# AgitPOV_WiFi.net
KiCad netlist of a schematic drawn in EAGLE
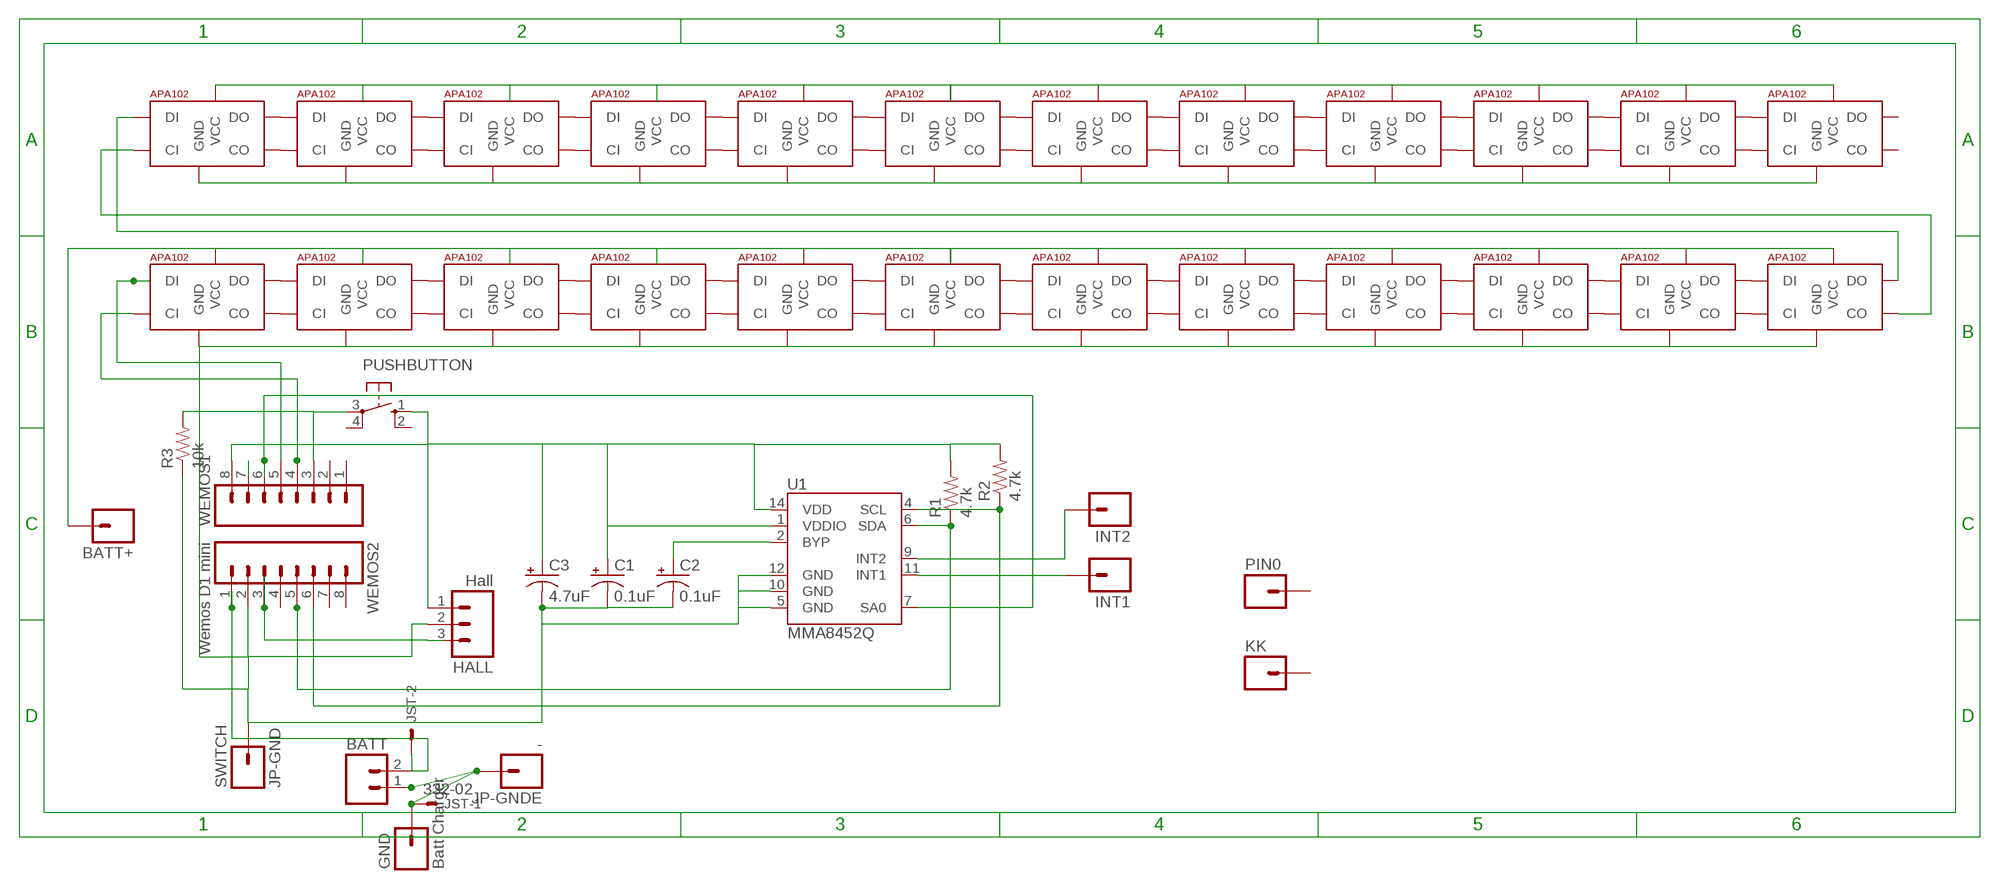
[diagram p0: schematic, sheet 1]

(export (version "E")
  (design (tool "Eeschema 10.0.6"))
  (components
    (comp (ref "BATT")
      (value "M02LOCK_LONGPADS")
      (footprint "eagle-import:1X02_LOCK_LONGPADS")
      (libsource (lib "eagle-import") (part "M02LOCK_LONGPADS"))
    )
    (comp (ref "BATT+")
      (value "M01PTH")
      (footprint "eagle-import:1X01")
      (libsource (lib "eagle-import") (part "M01PTH"))
    )
    (comp (ref "C1")
      (value "0.1uF")
      (footprint "eagle-import:EIA3216")
      (libsource (lib "eagle-import") (part "10UF-16V-10%(TANT)"))
    )
    (comp (ref "C2")
      (value "0.1uF")
      (footprint "eagle-import:EIA3216")
      (libsource (lib "eagle-import") (part "10UF-16V-10%(TANT)"))
    )
    (comp (ref "C3")
      (value "4.7uF")
      (footprint "eagle-import:EIA3216")
      (libsource (lib "eagle-import") (part "10UF-16V-10%(TANT)"))
    )
    (comp (ref "DEL1")
      (value "APA1025050")
      (footprint "eagle-import:APA102_5050")
      (libsource (lib "eagle-import") (part "APA1025050"))
    )
    (comp (ref "DEL2")
      (value "APA1025050")
      (footprint "eagle-import:APA102_5050")
      (libsource (lib "eagle-import") (part "APA1025050"))
    )
    (comp (ref "DEL3")
      (value "APA1025050")
      (footprint "eagle-import:APA102_5050")
      (libsource (lib "eagle-import") (part "APA1025050"))
    )
    (comp (ref "DEL4")
      (value "APA1025050")
      (footprint "eagle-import:APA102_5050")
      (libsource (lib "eagle-import") (part "APA1025050"))
    )
    (comp (ref "DEL5")
      (value "APA1025050")
      (footprint "eagle-import:APA102_5050")
      (libsource (lib "eagle-import") (part "APA1025050"))
    )
    (comp (ref "DEL6")
      (value "APA1025050")
      (footprint "eagle-import:APA102_5050")
      (libsource (lib "eagle-import") (part "APA1025050"))
    )
    (comp (ref "DEL7")
      (value "APA1025050")
      (footprint "eagle-import:APA102_5050")
      (libsource (lib "eagle-import") (part "APA1025050"))
    )
    (comp (ref "DEL8")
      (value "APA1025050")
      (footprint "eagle-import:APA102_5050")
      (libsource (lib "eagle-import") (part "APA1025050"))
    )
    (comp (ref "DEL9")
      (value "APA1025050")
      (footprint "eagle-import:APA102_5050")
      (libsource (lib "eagle-import") (part "APA1025050"))
    )
    (comp (ref "DEL10")
      (value "APA1025050")
      (footprint "eagle-import:APA102_5050")
      (libsource (lib "eagle-import") (part "APA1025050"))
    )
    (comp (ref "DEL11")
      (value "APA1025050")
      (footprint "eagle-import:APA102_5050")
      (libsource (lib "eagle-import") (part "APA1025050"))
    )
    (comp (ref "DEL12")
      (value "APA1025050")
      (footprint "eagle-import:APA102_5050")
      (libsource (lib "eagle-import") (part "APA1025050"))
    )
    (comp (ref "DEL13")
      (value "APA1025050")
      (footprint "eagle-import:APA102_5050")
      (libsource (lib "eagle-import") (part "APA1025050"))
    )
    (comp (ref "DEL15")
      (value "APA1025050")
      (footprint "eagle-import:APA102_5050")
      (libsource (lib "eagle-import") (part "APA1025050"))
    )
    (comp (ref "DEL16")
      (value "APA1025050")
      (footprint "eagle-import:APA102_5050")
      (libsource (lib "eagle-import") (part "APA1025050"))
    )
    (comp (ref "DEL17")
      (value "APA1025050")
      (footprint "eagle-import:APA102_5050")
      (libsource (lib "eagle-import") (part "APA1025050"))
    )
    (comp (ref "DEL18")
      (value "APA1025050")
      (footprint "eagle-import:APA102_5050")
      (libsource (lib "eagle-import") (part "APA1025050"))
    )
    (comp (ref "DEL19")
      (value "APA1025050")
      (footprint "eagle-import:APA102_5050")
      (libsource (lib "eagle-import") (part "APA1025050"))
    )
    (comp (ref "DEL20")
      (value "APA1025050")
      (footprint "eagle-import:APA102_5050")
      (libsource (lib "eagle-import") (part "APA1025050"))
    )
    (comp (ref "DEL21")
      (value "APA1025050")
      (footprint "eagle-import:APA102_5050")
      (libsource (lib "eagle-import") (part "APA1025050"))
    )
    (comp (ref "DEL22")
      (value "APA1025050")
      (footprint "eagle-import:APA102_5050")
      (libsource (lib "eagle-import") (part "APA1025050"))
    )
    (comp (ref "DEL23")
      (value "APA1025050")
      (footprint "eagle-import:APA102_5050")
      (libsource (lib "eagle-import") (part "APA1025050"))
    )
    (comp (ref "DEL24")
      (value "APA1025050")
      (footprint "eagle-import:APA102_5050")
      (libsource (lib "eagle-import") (part "APA1025050"))
    )
    (comp (ref "FFFFF")
      (value "APA1025050")
      (footprint "eagle-import:APA102_5050")
      (libsource (lib "eagle-import") (part "APA1025050"))
    )
    (comp (ref "GND")
      (value "Batt Charger")
      (footprint "eagle-import:1X01")
      (libsource (lib "eagle-import") (part "M01PTH"))
    )
    (comp (ref "HALL")
      (value "Hall")
      (footprint "eagle-import:1X03")
      (libsource (lib "eagle-import") (part "M03PTH"))
    )
    (comp (ref "INT1")
      (value "M01PTH")
      (footprint "eagle-import:1X01")
      (libsource (lib "eagle-import") (part "M01PTH"))
    )
    (comp (ref "INT2")
      (value "M01PTH")
      (footprint "eagle-import:1X01")
      (libsource (lib "eagle-import") (part "M01PTH"))
    )
    (comp (ref "JP-GND")
      (value "SWITCH")
      (footprint "eagle-import:1X01")
      (libsource (lib "eagle-import") (part "M01PTH"))
    )
    (comp (ref "JP-GNDE")
      (value "-")
      (footprint "eagle-import:1X01")
      (libsource (lib "eagle-import") (part "M01PTH"))
    )
    (comp (ref "JST")
      (value "332-02")
      (footprint "eagle-import:332-02")
      (libsource (lib "eagle-import") (part "332-02"))
    )
    (comp (ref "KK")
      (value "M01PTH")
      (footprint "eagle-import:1X01")
      (libsource (lib "eagle-import") (part "M01PTH"))
    )
    (comp (ref "PIN0")
      (value "M01PTH")
      (footprint "eagle-import:1X01")
      (libsource (lib "eagle-import") (part "M01PTH"))
    )
    (comp (ref "PUSHBUTTON")
      (value "10-XX")
      (footprint "eagle-import:B3F-10XX")
      (fields (field (name "MPN") "B3F-1000"))
      (libsource (lib "eagle-import") (part "10-XX"))
    )
    (comp (ref "R1")
      (value "4.7k")
      (footprint "eagle-import:1206")
      (libsource (lib "eagle-import") (part "RESISTOR1206"))
    )
    (comp (ref "R2")
      (value "4.7k")
      (footprint "eagle-import:1206")
      (libsource (lib "eagle-import") (part "RESISTOR1206"))
    )
    (comp (ref "R3")
      (value "10k")
      (footprint "eagle-import:1206")
      (libsource (lib "eagle-import") (part "RESISTOR1206"))
    )
    (comp (ref "U1")
      (value "MMA8452Q")
      (footprint "eagle-import:QFN-16_0.5MM")
      (libsource (lib "eagle-import") (part "MMA8452Q"))
    )
    (comp (ref "WEMOS1")
      (value "M08")
      (footprint "eagle-import:1X08_ROUND")
      (libsource (lib "eagle-import") (part "M08"))
    )
    (comp (ref "WEMOS2")
      (value "Wemos D1 mini")
      (footprint "eagle-import:1X08_ROUND")
      (libsource (lib "eagle-import") (part "M08"))
    )
  )
  (nets
    (net (code "1") (name "/5V") (class "Default")
      (node (ref "BATT") (pin "2") (pinfunction "2_2") (pintype "passive"))
      (node (ref "BATT+") (pin "1") (pinfunction "1_1") (pintype "passive"))
      (node (ref "DEL1") (pin "1") (pinfunction "VCC_1") (pintype "bidirectional"))
      (node (ref "DEL10") (pin "1") (pinfunction "VCC_1") (pintype "bidirectional"))
      (node (ref "DEL11") (pin "1") (pinfunction "VCC_1") (pintype "bidirectional"))
      (node (ref "DEL12") (pin "1") (pinfunction "VCC_1") (pintype "bidirectional"))
      (node (ref "DEL13") (pin "1") (pinfunction "VCC_1") (pintype "bidirectional"))
      (node (ref "DEL15") (pin "1") (pinfunction "VCC_1") (pintype "bidirectional"))
      (node (ref "DEL16") (pin "1") (pinfunction "VCC_1") (pintype "bidirectional"))
      (node (ref "DEL17") (pin "1") (pinfunction "VCC_1") (pintype "bidirectional"))
      (node (ref "DEL18") (pin "1") (pinfunction "VCC_1") (pintype "bidirectional"))
      (node (ref "DEL19") (pin "1") (pinfunction "VCC_1") (pintype "bidirectional"))
      (node (ref "DEL2") (pin "1") (pinfunction "VCC_1") (pintype "bidirectional"))
      (node (ref "DEL20") (pin "1") (pinfunction "VCC_1") (pintype "bidirectional"))
      (node (ref "DEL21") (pin "1") (pinfunction "VCC_1") (pintype "bidirectional"))
      (node (ref "DEL22") (pin "1") (pinfunction "VCC_1") (pintype "bidirectional"))
      (node (ref "DEL23") (pin "1") (pinfunction "VCC_1") (pintype "bidirectional"))
      (node (ref "DEL24") (pin "1") (pinfunction "VCC_1") (pintype "bidirectional"))
      (node (ref "DEL3") (pin "1") (pinfunction "VCC_1") (pintype "bidirectional"))
      (node (ref "DEL4") (pin "1") (pinfunction "VCC_1") (pintype "bidirectional"))
      (node (ref "DEL5") (pin "1") (pinfunction "VCC_1") (pintype "bidirectional"))
      (node (ref "DEL6") (pin "1") (pinfunction "VCC_1") (pintype "bidirectional"))
      (node (ref "DEL7") (pin "1") (pinfunction "VCC_1") (pintype "bidirectional"))
      (node (ref "DEL8") (pin "1") (pinfunction "VCC_1") (pintype "bidirectional"))
      (node (ref "DEL9") (pin "1") (pinfunction "VCC_1") (pintype "bidirectional"))
      (node (ref "FFFFF") (pin "1") (pinfunction "VCC_1") (pintype "bidirectional"))
      (node (ref "JST") (pin "2") (pinfunction "S_2") (pintype "passive"))
      (node (ref "WEMOS2") (pin "1") (pinfunction "1_1") (pintype "passive"))
    )
    (net (code "2") (name "/GND") (class "Default")
      (node (ref "C1") (pin "C") (pinfunction "-_C") (pintype "passive"))
      (node (ref "C2") (pin "C") (pinfunction "-_C") (pintype "passive"))
      (node (ref "C3") (pin "C") (pinfunction "-_C") (pintype "passive"))
      (node (ref "DEL1") (pin "6") (pinfunction "GND_6") (pintype "bidirectional"))
      (node (ref "DEL10") (pin "6") (pinfunction "GND_6") (pintype "bidirectional"))
      (node (ref "DEL11") (pin "6") (pinfunction "GND_6") (pintype "bidirectional"))
      (node (ref "DEL12") (pin "6") (pinfunction "GND_6") (pintype "bidirectional"))
      (node (ref "DEL13") (pin "6") (pinfunction "GND_6") (pintype "bidirectional"))
      (node (ref "DEL15") (pin "6") (pinfunction "GND_6") (pintype "bidirectional"))
      (node (ref "DEL16") (pin "6") (pinfunction "GND_6") (pintype "bidirectional"))
      (node (ref "DEL17") (pin "6") (pinfunction "GND_6") (pintype "bidirectional"))
      (node (ref "DEL18") (pin "6") (pinfunction "GND_6") (pintype "bidirectional"))
      (node (ref "DEL19") (pin "6") (pinfunction "GND_6") (pintype "bidirectional"))
      (node (ref "DEL2") (pin "6") (pinfunction "GND_6") (pintype "bidirectional"))
      (node (ref "DEL20") (pin "6") (pinfunction "GND_6") (pintype "bidirectional"))
      (node (ref "DEL21") (pin "6") (pinfunction "GND_6") (pintype "bidirectional"))
      (node (ref "DEL22") (pin "6") (pinfunction "GND_6") (pintype "bidirectional"))
      (node (ref "DEL23") (pin "6") (pinfunction "GND_6") (pintype "bidirectional"))
      (node (ref "DEL24") (pin "6") (pinfunction "GND_6") (pintype "bidirectional"))
      (node (ref "DEL3") (pin "6") (pinfunction "GND_6") (pintype "bidirectional"))
      (node (ref "DEL4") (pin "6") (pinfunction "GND_6") (pintype "bidirectional"))
      (node (ref "DEL5") (pin "6") (pinfunction "GND_6") (pintype "bidirectional"))
      (node (ref "DEL6") (pin "6") (pinfunction "GND_6") (pintype "bidirectional"))
      (node (ref "DEL7") (pin "6") (pinfunction "GND_6") (pintype "bidirectional"))
      (node (ref "DEL8") (pin "6") (pinfunction "GND_6") (pintype "bidirectional"))
      (node (ref "DEL9") (pin "6") (pinfunction "GND_6") (pintype "bidirectional"))
      (node (ref "FFFFF") (pin "6") (pinfunction "GND_6") (pintype "bidirectional"))
      (node (ref "HALL") (pin "2") (pinfunction "2_2") (pintype "passive"))
      (node (ref "JP-GND") (pin "1") (pinfunction "1_1") (pintype "passive"))
      (node (ref "R3") (pin "1") (pinfunction "1_1") (pintype "passive"))
      (node (ref "U1") (pin "10") (pinfunction "GND_10") (pintype "bidirectional"))
      (node (ref "U1") (pin "12") (pinfunction "GND_12") (pintype "bidirectional"))
      (node (ref "U1") (pin "5") (pinfunction "GND_5") (pintype "bidirectional"))
      (node (ref "WEMOS2") (pin "2") (pinfunction "2_2") (pintype "passive"))
    )
    (net (code "3") (name "Net-(C1-+)") (class "Default")
      (node (ref "C1") (pin "A") (pinfunction "+_A") (pintype "passive"))
      (node (ref "C3") (pin "A") (pinfunction "+_A") (pintype "passive"))
      (node (ref "HALL") (pin "1") (pinfunction "1_1") (pintype "passive"))
      (node (ref "PUSHBUTTON") (pin "1") (pinfunction "S_1") (pintype "passive"))
      (node (ref "R1") (pin "2") (pinfunction "2_2") (pintype "passive"))
      (node (ref "R2") (pin "2") (pinfunction "2_2") (pintype "passive"))
      (node (ref "U1") (pin "1") (pinfunction "VDDIO_1") (pintype "bidirectional"))
      (node (ref "U1") (pin "14") (pinfunction "VDD_14") (pintype "bidirectional"))
      (node (ref "WEMOS1") (pin "8") (pinfunction "8_8") (pintype "passive"))
    )
    (net (code "4") (name "Net-(C2-+)") (class "Default")
      (node (ref "C2") (pin "A") (pinfunction "+_A") (pintype "passive"))
      (node (ref "U1") (pin "2") (pinfunction "BYP_2") (pintype "bidirectional"))
    )
    (net (code "5") (name "Net-(DEL1-CI)") (class "Default")
      (node (ref "DEL1") (pin "5") (pinfunction "CI_5") (pintype "bidirectional"))
      (node (ref "WEMOS1") (pin "4") (pinfunction "4_4") (pintype "passive"))
    )
    (net (code "6") (name "Net-(DEL1-CO)") (class "Default")
      (node (ref "DEL1") (pin "2") (pinfunction "CO_2") (pintype "bidirectional"))
      (node (ref "DEL2") (pin "5") (pinfunction "CI_5") (pintype "bidirectional"))
    )
    (net (code "7") (name "Net-(DEL1-DI)") (class "Default")
      (node (ref "DEL1") (pin "4") (pinfunction "DI_4") (pintype "bidirectional"))
      (node (ref "WEMOS1") (pin "5") (pinfunction "5_5") (pintype "passive"))
    )
    (net (code "8") (name "Net-(DEL1-DO)") (class "Default")
      (node (ref "DEL1") (pin "3") (pinfunction "DO_3") (pintype "bidirectional"))
      (node (ref "DEL2") (pin "4") (pinfunction "DI_4") (pintype "bidirectional"))
    )
    (net (code "9") (name "Net-(DEL2-CO)") (class "Default")
      (node (ref "DEL2") (pin "2") (pinfunction "CO_2") (pintype "bidirectional"))
      (node (ref "DEL3") (pin "5") (pinfunction "CI_5") (pintype "bidirectional"))
    )
    (net (code "10") (name "Net-(DEL2-DO)") (class "Default")
      (node (ref "DEL2") (pin "3") (pinfunction "DO_3") (pintype "bidirectional"))
      (node (ref "DEL3") (pin "4") (pinfunction "DI_4") (pintype "bidirectional"))
    )
    (net (code "11") (name "Net-(DEL3-CO)") (class "Default")
      (node (ref "DEL3") (pin "2") (pinfunction "CO_2") (pintype "bidirectional"))
      (node (ref "DEL4") (pin "5") (pinfunction "CI_5") (pintype "bidirectional"))
    )
    (net (code "12") (name "Net-(DEL3-DO)") (class "Default")
      (node (ref "DEL3") (pin "3") (pinfunction "DO_3") (pintype "bidirectional"))
      (node (ref "DEL4") (pin "4") (pinfunction "DI_4") (pintype "bidirectional"))
    )
    (net (code "13") (name "Net-(DEL4-CO)") (class "Default")
      (node (ref "DEL4") (pin "2") (pinfunction "CO_2") (pintype "bidirectional"))
      (node (ref "DEL5") (pin "5") (pinfunction "CI_5") (pintype "bidirectional"))
    )
    (net (code "14") (name "Net-(DEL4-DO)") (class "Default")
      (node (ref "DEL4") (pin "3") (pinfunction "DO_3") (pintype "bidirectional"))
      (node (ref "DEL5") (pin "4") (pinfunction "DI_4") (pintype "bidirectional"))
    )
    (net (code "15") (name "Net-(DEL5-CO)") (class "Default")
      (node (ref "DEL5") (pin "2") (pinfunction "CO_2") (pintype "bidirectional"))
      (node (ref "DEL6") (pin "5") (pinfunction "CI_5") (pintype "bidirectional"))
    )
    (net (code "16") (name "Net-(DEL5-DO)") (class "Default")
      (node (ref "DEL5") (pin "3") (pinfunction "DO_3") (pintype "bidirectional"))
      (node (ref "DEL6") (pin "4") (pinfunction "DI_4") (pintype "bidirectional"))
    )
    (net (code "17") (name "Net-(DEL6-CO)") (class "Default")
      (node (ref "DEL6") (pin "2") (pinfunction "CO_2") (pintype "bidirectional"))
      (node (ref "DEL7") (pin "5") (pinfunction "CI_5") (pintype "bidirectional"))
    )
    (net (code "18") (name "Net-(DEL6-DO)") (class "Default")
      (node (ref "DEL6") (pin "3") (pinfunction "DO_3") (pintype "bidirectional"))
      (node (ref "DEL7") (pin "4") (pinfunction "DI_4") (pintype "bidirectional"))
    )
    (net (code "19") (name "Net-(DEL7-CO)") (class "Default")
      (node (ref "DEL7") (pin "2") (pinfunction "CO_2") (pintype "bidirectional"))
      (node (ref "DEL8") (pin "5") (pinfunction "CI_5") (pintype "bidirectional"))
    )
    (net (code "20") (name "Net-(DEL7-DO)") (class "Default")
      (node (ref "DEL7") (pin "3") (pinfunction "DO_3") (pintype "bidirectional"))
      (node (ref "DEL8") (pin "4") (pinfunction "DI_4") (pintype "bidirectional"))
    )
    (net (code "21") (name "Net-(DEL8-CO)") (class "Default")
      (node (ref "DEL8") (pin "2") (pinfunction "CO_2") (pintype "bidirectional"))
      (node (ref "DEL9") (pin "5") (pinfunction "CI_5") (pintype "bidirectional"))
    )
    (net (code "22") (name "Net-(DEL8-DO)") (class "Default")
      (node (ref "DEL8") (pin "3") (pinfunction "DO_3") (pintype "bidirectional"))
      (node (ref "DEL9") (pin "4") (pinfunction "DI_4") (pintype "bidirectional"))
    )
    (net (code "23") (name "Net-(DEL10-CI)") (class "Default")
      (node (ref "DEL10") (pin "5") (pinfunction "CI_5") (pintype "bidirectional"))
      (node (ref "DEL9") (pin "2") (pinfunction "CO_2") (pintype "bidirectional"))
    )
    (net (code "24") (name "Net-(DEL10-CO)") (class "Default")
      (node (ref "DEL10") (pin "2") (pinfunction "CO_2") (pintype "bidirectional"))
      (node (ref "DEL11") (pin "5") (pinfunction "CI_5") (pintype "bidirectional"))
    )
    (net (code "25") (name "Net-(DEL10-DI)") (class "Default")
      (node (ref "DEL10") (pin "4") (pinfunction "DI_4") (pintype "bidirectional"))
      (node (ref "DEL9") (pin "3") (pinfunction "DO_3") (pintype "bidirectional"))
    )
    (net (code "26") (name "Net-(DEL10-DO)") (class "Default")
      (node (ref "DEL10") (pin "3") (pinfunction "DO_3") (pintype "bidirectional"))
      (node (ref "DEL11") (pin "4") (pinfunction "DI_4") (pintype "bidirectional"))
    )
    (net (code "27") (name "Net-(DEL11-CO)") (class "Default")
      (node (ref "DEL11") (pin "2") (pinfunction "CO_2") (pintype "bidirectional"))
      (node (ref "DEL12") (pin "5") (pinfunction "CI_5") (pintype "bidirectional"))
    )
    (net (code "28") (name "Net-(DEL11-DO)") (class "Default")
      (node (ref "DEL11") (pin "3") (pinfunction "DO_3") (pintype "bidirectional"))
      (node (ref "DEL12") (pin "4") (pinfunction "DI_4") (pintype "bidirectional"))
    )
    (net (code "29") (name "Net-(DEL12-CO)") (class "Default")
      (node (ref "DEL12") (pin "2") (pinfunction "CO_2") (pintype "bidirectional"))
      (node (ref "DEL13") (pin "5") (pinfunction "CI_5") (pintype "bidirectional"))
    )
    (net (code "30") (name "Net-(DEL12-DO)") (class "Default")
      (node (ref "DEL12") (pin "3") (pinfunction "DO_3") (pintype "bidirectional"))
      (node (ref "DEL13") (pin "4") (pinfunction "DI_4") (pintype "bidirectional"))
    )
    (net (code "31") (name "Net-(DEL13-CO)") (class "Default")
      (node (ref "DEL13") (pin "2") (pinfunction "CO_2") (pintype "bidirectional"))
      (node (ref "FFFFF") (pin "5") (pinfunction "CI_5") (pintype "bidirectional"))
    )
    (net (code "32") (name "Net-(DEL13-DO)") (class "Default")
      (node (ref "DEL13") (pin "3") (pinfunction "DO_3") (pintype "bidirectional"))
      (node (ref "FFFFF") (pin "4") (pinfunction "DI_4") (pintype "bidirectional"))
    )
    (net (code "33") (name "Net-(DEL15-CI)") (class "Default")
      (node (ref "DEL15") (pin "5") (pinfunction "CI_5") (pintype "bidirectional"))
      (node (ref "FFFFF") (pin "2") (pinfunction "CO_2") (pintype "bidirectional"))
    )
    (net (code "34") (name "Net-(DEL15-CO)") (class "Default")
      (node (ref "DEL15") (pin "2") (pinfunction "CO_2") (pintype "bidirectional"))
      (node (ref "DEL16") (pin "5") (pinfunction "CI_5") (pintype "bidirectional"))
    )
    (net (code "35") (name "Net-(DEL15-DI)") (class "Default")
      (node (ref "DEL15") (pin "4") (pinfunction "DI_4") (pintype "bidirectional"))
      (node (ref "FFFFF") (pin "3") (pinfunction "DO_3") (pintype "bidirectional"))
    )
    (net (code "36") (name "Net-(DEL15-DO)") (class "Default")
      (node (ref "DEL15") (pin "3") (pinfunction "DO_3") (pintype "bidirectional"))
      (node (ref "DEL16") (pin "4") (pinfunction "DI_4") (pintype "bidirectional"))
    )
    (net (code "37") (name "Net-(DEL16-CO)") (class "Default")
      (node (ref "DEL16") (pin "2") (pinfunction "CO_2") (pintype "bidirectional"))
      (node (ref "DEL17") (pin "5") (pinfunction "CI_5") (pintype "bidirectional"))
    )
    (net (code "38") (name "Net-(DEL16-DO)") (class "Default")
      (node (ref "DEL16") (pin "3") (pinfunction "DO_3") (pintype "bidirectional"))
      (node (ref "DEL17") (pin "4") (pinfunction "DI_4") (pintype "bidirectional"))
    )
    (net (code "39") (name "Net-(DEL17-CO)") (class "Default")
      (node (ref "DEL17") (pin "2") (pinfunction "CO_2") (pintype "bidirectional"))
      (node (ref "DEL18") (pin "5") (pinfunction "CI_5") (pintype "bidirectional"))
    )
    (net (code "40") (name "Net-(DEL17-DO)") (class "Default")
      (node (ref "DEL17") (pin "3") (pinfunction "DO_3") (pintype "bidirectional"))
      (node (ref "DEL18") (pin "4") (pinfunction "DI_4") (pintype "bidirectional"))
    )
    (net (code "41") (name "Net-(DEL18-CO)") (class "Default")
      (node (ref "DEL18") (pin "2") (pinfunction "CO_2") (pintype "bidirectional"))
      (node (ref "DEL19") (pin "5") (pinfunction "CI_5") (pintype "bidirectional"))
    )
    (net (code "42") (name "Net-(DEL18-DO)") (class "Default")
      (node (ref "DEL18") (pin "3") (pinfunction "DO_3") (pintype "bidirectional"))
      (node (ref "DEL19") (pin "4") (pinfunction "DI_4") (pintype "bidirectional"))
    )
    (net (code "43") (name "Net-(DEL19-CO)") (class "Default")
      (node (ref "DEL19") (pin "2") (pinfunction "CO_2") (pintype "bidirectional"))
      (node (ref "DEL20") (pin "5") (pinfunction "CI_5") (pintype "bidirectional"))
    )
    (net (code "44") (name "Net-(DEL19-DO)") (class "Default")
      (node (ref "DEL19") (pin "3") (pinfunction "DO_3") (pintype "bidirectional"))
      (node (ref "DEL20") (pin "4") (pinfunction "DI_4") (pintype "bidirectional"))
    )
    (net (code "45") (name "Net-(DEL20-CO)") (class "Default")
      (node (ref "DEL20") (pin "2") (pinfunction "CO_2") (pintype "bidirectional"))
      (node (ref "DEL21") (pin "5") (pinfunction "CI_5") (pintype "bidirectional"))
    )
    (net (code "46") (name "Net-(DEL20-DO)") (class "Default")
      (node (ref "DEL20") (pin "3") (pinfunction "DO_3") (pintype "bidirectional"))
      (node (ref "DEL21") (pin "4") (pinfunction "DI_4") (pintype "bidirectional"))
    )
    (net (code "47") (name "Net-(DEL21-CO)") (class "Default")
      (node (ref "DEL21") (pin "2") (pinfunction "CO_2") (pintype "bidirectional"))
      (node (ref "DEL22") (pin "5") (pinfunction "CI_5") (pintype "bidirectional"))
    )
    (net (code "48") (name "Net-(DEL21-DO)") (class "Default")
      (node (ref "DEL21") (pin "3") (pinfunction "DO_3") (pintype "bidirectional"))
      (node (ref "DEL22") (pin "4") (pinfunction "DI_4") (pintype "bidirectional"))
    )
    (net (code "49") (name "Net-(DEL22-CO)") (class "Default")
      (node (ref "DEL22") (pin "2") (pinfunction "CO_2") (pintype "bidirectional"))
      (node (ref "DEL23") (pin "5") (pinfunction "CI_5") (pintype "bidirectional"))
    )
    (net (code "50") (name "Net-(DEL22-DO)") (class "Default")
      (node (ref "DEL22") (pin "3") (pinfunction "DO_3") (pintype "bidirectional"))
      (node (ref "DEL23") (pin "4") (pinfunction "DI_4") (pintype "bidirectional"))
    )
    (net (code "51") (name "Net-(DEL23-CO)") (class "Default")
      (node (ref "DEL23") (pin "2") (pinfunction "CO_2") (pintype "bidirectional"))
      (node (ref "DEL24") (pin "5") (pinfunction "CI_5") (pintype "bidirectional"))
    )
    (net (code "52") (name "Net-(DEL23-DO)") (class "Default")
      (node (ref "DEL23") (pin "3") (pinfunction "DO_3") (pintype "bidirectional"))
      (node (ref "DEL24") (pin "4") (pinfunction "DI_4") (pintype "bidirectional"))
    )
    (net (code "53") (name "Net-(HALL-Pad3)") (class "Default")
      (node (ref "HALL") (pin "3") (pinfunction "3_3") (pintype "passive"))
      (node (ref "WEMOS2") (pin "3") (pinfunction "3_3") (pintype "passive"))
    )
    (net (code "54") (name "Net-(JSTA-S)") (class "Default")
      (node (ref "BATT") (pin "1") (pinfunction "1_1") (pintype "passive"))
      (node (ref "GND") (pin "1") (pinfunction "1_1") (pintype "passive"))
      (node (ref "JP-GNDE") (pin "1") (pinfunction "1_1") (pintype "passive"))
      (node (ref "JST") (pin "1") (pinfunction "S_1") (pintype "passive"))
    )
    (net (code "55") (name "Net-(PUSHBUTTON-P)") (class "Default")
      (node (ref "PUSHBUTTON") (pin "3") (pinfunction "P_3") (pintype "passive"))
      (node (ref "R3") (pin "2") (pinfunction "2_2") (pintype "passive"))
      (node (ref "WEMOS1") (pin "3") (pinfunction "3_3") (pintype "passive"))
    )
    (net (code "56") (name "Net-(U1-INT1)") (class "Default")
      (node (ref "INT1") (pin "1") (pinfunction "1_1") (pintype "passive"))
      (node (ref "U1") (pin "11") (pinfunction "INT1_11") (pintype "bidirectional"))
    )
    (net (code "57") (name "Net-(U1-INT2)") (class "Default")
      (node (ref "INT2") (pin "1") (pinfunction "1_1") (pintype "passive"))
      (node (ref "U1") (pin "9") (pinfunction "INT2_9") (pintype "bidirectional"))
    )
    (net (code "58") (name "Net-(U1-SA0)") (class "Default")
      (node (ref "U1") (pin "7") (pinfunction "SA0_7") (pintype "bidirectional"))
      (node (ref "WEMOS1") (pin "6") (pinfunction "6_6") (pintype "passive"))
    )
    (net (code "59") (name "Net-(U1-SCL)") (class "Default")
      (node (ref "R2") (pin "1") (pinfunction "1_1") (pintype "passive"))
      (node (ref "U1") (pin "4") (pinfunction "SCL_4") (pintype "bidirectional"))
      (node (ref "WEMOS2") (pin "6") (pinfunction "6_6") (pintype "passive"))
    )
    (net (code "60") (name "Net-(U1-SDA)") (class "Default")
      (node (ref "R1") (pin "1") (pinfunction "1_1") (pintype "passive"))
      (node (ref "U1") (pin "6") (pinfunction "SDA_6") (pintype "bidirectional"))
      (node (ref "WEMOS2") (pin "5") (pinfunction "5_5") (pintype "passive"))
    )
    (net (code "61") (name "unconnected-(DEL24-CO-Pad2)") (class "Default")
      (node (ref "DEL24") (pin "2") (pinfunction "CO_2") (pintype "bidirectional"))
    )
    (net (code "62") (name "unconnected-(DEL24-DO-Pad3)") (class "Default")
      (node (ref "DEL24") (pin "3") (pinfunction "DO_3") (pintype "bidirectional"))
    )
    (net (code "63") (name "unconnected-(KK-Pad1)") (class "Default")
      (node (ref "KK") (pin "1") (pinfunction "1_1") (pintype "passive"))
    )
    (net (code "64") (name "unconnected-(PIN0-Pad1)") (class "Default")
      (node (ref "PIN0") (pin "1") (pinfunction "1_1") (pintype "passive"))
    )
    (net (code "65") (name "unconnected-(PUSHBUTTON-P1-Pad4)") (class "Default")
      (node (ref "PUSHBUTTON") (pin "4") (pinfunction "P1_4") (pintype "passive"))
    )
    (net (code "66") (name "unconnected-(PUSHBUTTON-S1-Pad2)") (class "Default")
      (node (ref "PUSHBUTTON") (pin "2") (pinfunction "S1_2") (pintype "passive"))
    )
    (net (code "67") (name "unconnected-(WEMOS1-Pad1)") (class "Default")
      (node (ref "WEMOS1") (pin "1") (pinfunction "1_1") (pintype "passive"))
    )
    (net (code "68") (name "unconnected-(WEMOS1-Pad2)") (class "Default")
      (node (ref "WEMOS1") (pin "2") (pinfunction "2_2") (pintype "passive"))
    )
    (net (code "69") (name "unconnected-(WEMOS1-Pad7)") (class "Default")
      (node (ref "WEMOS1") (pin "7") (pinfunction "7_7") (pintype "passive"))
    )
    (net (code "70") (name "unconnected-(WEMOS2-Pad4)") (class "Default")
      (node (ref "WEMOS2") (pin "4") (pinfunction "4_4") (pintype "passive"))
    )
    (net (code "71") (name "unconnected-(WEMOS2-Pad7)") (class "Default")
      (node (ref "WEMOS2") (pin "7") (pinfunction "7_7") (pintype "passive"))
    )
    (net (code "72") (name "unconnected-(WEMOS2-Pad8)") (class "Default")
      (node (ref "WEMOS2") (pin "8") (pinfunction "8_8") (pintype "passive"))
    )
  )
)
